# template_atmega328p.net
KiCad netlist of a schematic drawn in EAGLE
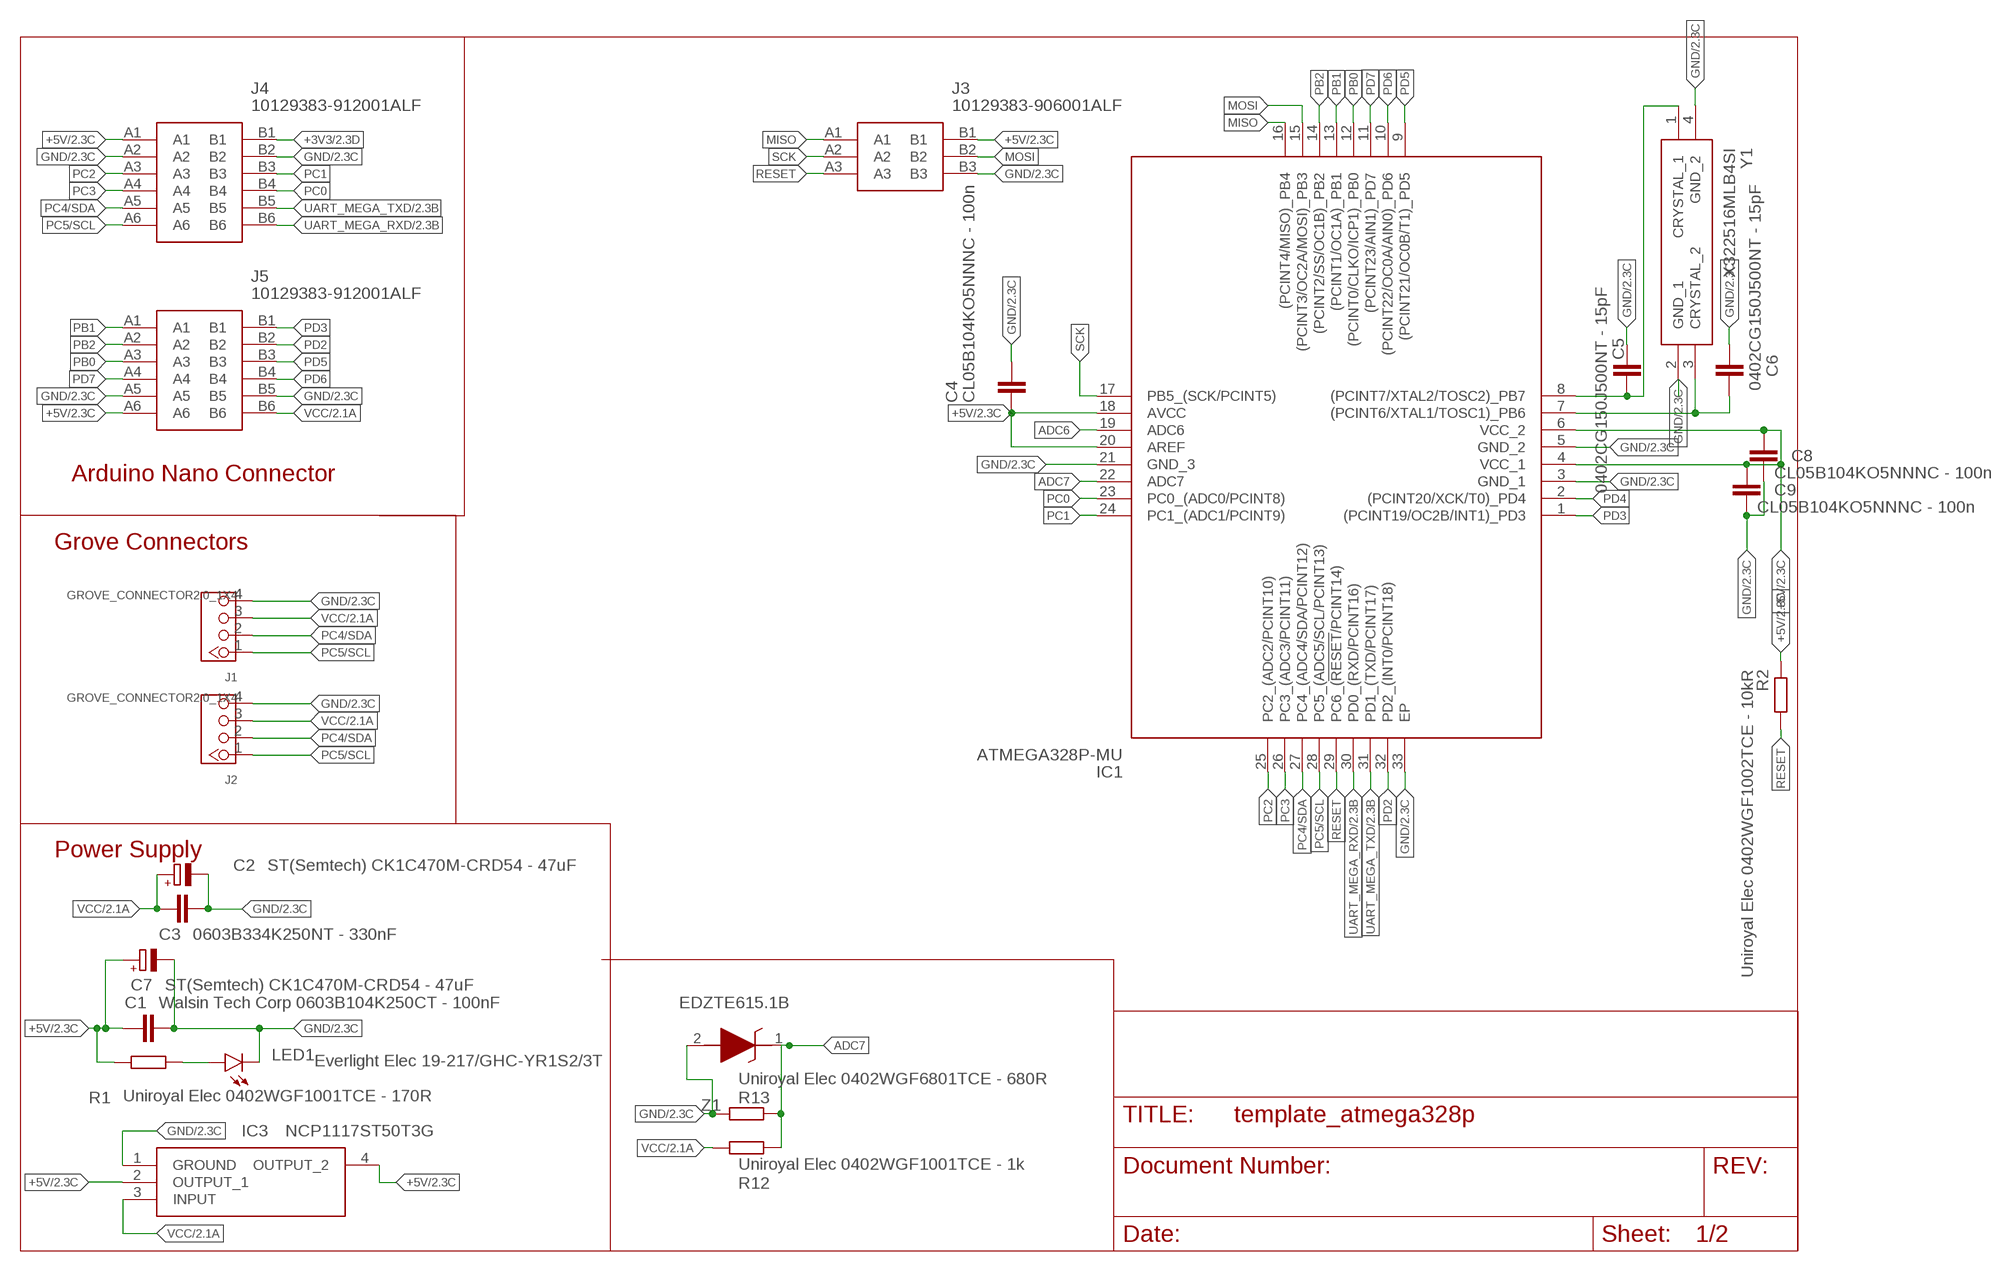
[diagram p0: schematic, sheet 1]
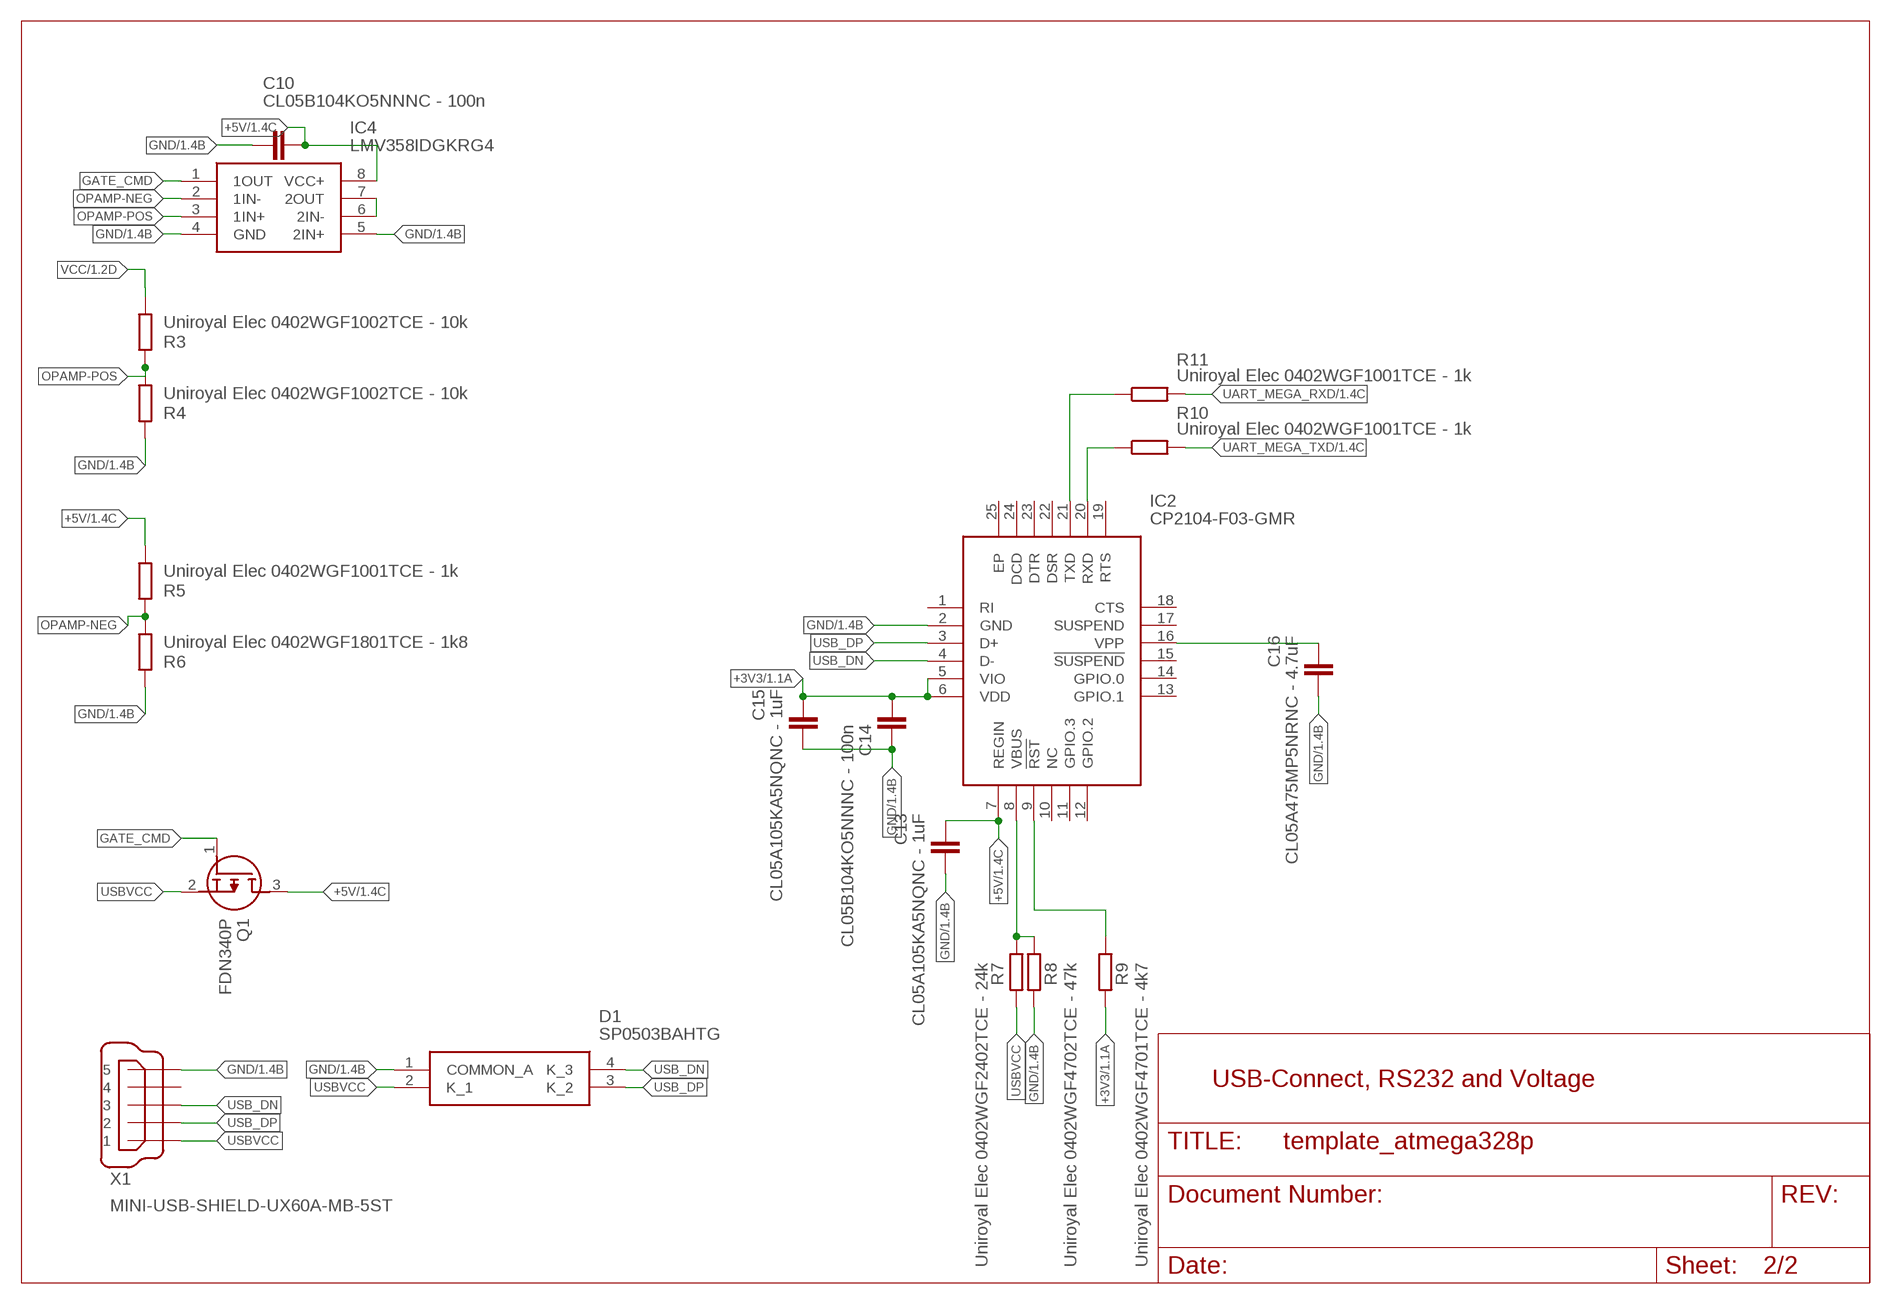
[diagram p1: schematic, sheet 2]

(export (version "E")
  (design (tool "Eeschema 10.0.6"))
  (components
    (comp (ref "C1")
      (value "Walsin Tech Corp 0603B104K250CT - 100nF")
      (footprint "eagle-import:C0603")
      (libsource (lib "eagle-import") (part "C-EUC0603"))
    )
    (comp (ref "C2")
      (value "ST(Semtech) CK1C470M-CRD54 - 47uF")
      (footprint "eagle-import:PANASONIC_C")
      (libsource (lib "eagle-import") (part "CPOL-EUC"))
    )
    (comp (ref "C3")
      (value "0603B334K250NT - 330nF")
      (footprint "eagle-import:C0603")
      (libsource (lib "eagle-import") (part "C-EUC0603"))
    )
    (comp (ref "C4")
      (value "CL05B104KO5NNNC - 100n")
      (footprint "eagle-import:C0402")
      (libsource (lib "eagle-import") (part "C-EUC0402"))
    )
    (comp (ref "C5")
      (value "0402CG150J500NT - 15pF")
      (footprint "eagle-import:C0402")
      (libsource (lib "eagle-import") (part "C-EUC0402"))
    )
    (comp (ref "C6")
      (value "0402CG150J500NT - 15pF")
      (footprint "eagle-import:C0402")
      (libsource (lib "eagle-import") (part "C-EUC0402"))
    )
    (comp (ref "C7")
      (value "ST(Semtech) CK1C470M-CRD54 - 47uF")
      (footprint "eagle-import:PANASONIC_C")
      (libsource (lib "eagle-import") (part "CPOL-EUC"))
    )
    (comp (ref "C8")
      (value "CL05B104KO5NNNC - 100n")
      (footprint "eagle-import:C0402")
      (libsource (lib "eagle-import") (part "C-EUC0402"))
    )
    (comp (ref "C9")
      (value "CL05B104KO5NNNC - 100n")
      (footprint "eagle-import:C0402")
      (libsource (lib "eagle-import") (part "C-EUC0402"))
    )
    (comp (ref "IC1")
      (value "ATMEGA328P-MU")
      (footprint "eagle-import:QFN50P500X500X100-33N")
      (fields (field (name "MOUSER_PART_NUMBER") "556-ATMEGA328P-MU"))
      (libsource (lib "eagle-import") (part "ATMEGA328P-MU"))
    )
    (comp (ref "IC3")
      (value "NCP1117ST50T3G")
      (footprint "eagle-import:SOT230P700X180-4N@1")
      (fields (field (name "MOUSER_PART_NUMBER") "863-NCP1117ST50T3G"))
      (libsource (lib "eagle-import") (part "NCP1117ST50T3G"))
    )
    (comp (ref "J1")
      (value "GROVE_CONNECTOR2.0_1X4")
      (footprint "eagle-import:2.0_1X4_STRAIGHT")
      (libsource (lib "eagle-import") (part "GROVE_CONNECTOR2.0_1X4"))
    )
    (comp (ref "J2")
      (value "GROVE_CONNECTOR2.0_1X4")
      (footprint "eagle-import:2.0_1X4_STRAIGHT")
      (libsource (lib "eagle-import") (part "GROVE_CONNECTOR2.0_1X4"))
    )
    (comp (ref "J3")
      (value "10129383-906001ALF")
      (footprint "eagle-import:10129383906001ALF")
      (fields (field (name "MOUSER_PART_NUMBER") "649-1012938390601ALF"))
      (libsource (lib "eagle-import") (part "10129383-906001ALF"))
    )
    (comp (ref "J4")
      (value "10129383-912001ALF")
      (footprint "eagle-import:10129383912001ALF")
      (fields (field (name "MOUSER_PART_NUMBER") "649-1012938391201ALF"))
      (libsource (lib "eagle-import") (part "10129383-912001ALF"))
    )
    (comp (ref "J5")
      (value "10129383-912001ALF")
      (footprint "eagle-import:10129383912001ALF")
      (fields (field (name "MOUSER_PART_NUMBER") "649-1012938391201ALF"))
      (libsource (lib "eagle-import") (part "10129383-912001ALF"))
    )
    (comp (ref "LED1")
      (value "Everlight Elec 19-217/GHC-YR1S2/3T")
      (footprint "eagle-import:CHIPLED_0603")
      (libsource (lib "eagle-import") (part "LEDCHIPLED_0603"))
    )
    (comp (ref "R1")
      (value "Uniroyal Elec 0402WGF1001TCE - 170R")
      (footprint "eagle-import:R0402")
      (libsource (lib "eagle-import") (part "R-EU_R0402"))
    )
    (comp (ref "R2")
      (value "Uniroyal Elec 0402WGF1002TCE - 10kR")
      (footprint "eagle-import:R0402")
      (libsource (lib "eagle-import") (part "R-EU_R0402"))
    )
    (comp (ref "R12")
      (value "Uniroyal Elec 0402WGF1001TCE - 1k")
      (footprint "eagle-import:R0402")
      (libsource (lib "eagle-import") (part "R-EU_R0402"))
    )
    (comp (ref "R13")
      (value "Uniroyal Elec 0402WGF6801TCE - 680R")
      (footprint "eagle-import:R0402")
      (libsource (lib "eagle-import") (part "R-EU_R0402"))
    )
    (comp (ref "Y1")
      (value "X322516MLB4SI")
      (footprint "eagle-import:X322516MLB4SI")
      (libsource (lib "eagle-import") (part "X322516MLB4SI"))
    )
    (comp (ref "Z1")
      (value "EDZTE615.1B")
      (footprint "eagle-import:EMD2")
      (fields (field (name "MOUSER_PART_NUMBER") "755-EDZTE615.1B"))
      (libsource (lib "eagle-import") (part "EDZTE615.1B"))
    )
    (comp (ref "C10")
      (value "CL05B104KO5NNNC - 100n")
      (footprint "eagle-import:C0402")
      (libsource (lib "eagle-import") (part "C-EUC0402"))
    )
    (comp (ref "C13")
      (value "CL05A105KA5NQNC - 1uF")
      (footprint "eagle-import:C0402")
      (libsource (lib "eagle-import") (part "C-EUC0402"))
    )
    (comp (ref "C14")
      (value "CL05B104KO5NNNC - 100n")
      (footprint "eagle-import:C0402")
      (libsource (lib "eagle-import") (part "C-EUC0402"))
    )
    (comp (ref "C15")
      (value "CL05A105KA5NQNC - 1uF")
      (footprint "eagle-import:C0402")
      (libsource (lib "eagle-import") (part "C-EUC0402"))
    )
    (comp (ref "C16")
      (value "CL05A475MP5NRNC - 4.7uF")
      (footprint "eagle-import:C0402")
      (libsource (lib "eagle-import") (part "C-EUC0402"))
    )
    (comp (ref "D1")
      (value "SP0503BAHTG")
      (footprint "eagle-import:SP0503BAHTG")
      (fields (field (name "MOUSER_PART_NUMBER") "576-SP0503BAHTG"))
      (libsource (lib "eagle-import") (part "SP0503BAHTG"))
    )
    (comp (ref "IC2")
      (value "CP2104-F03-GMR")
      (footprint "eagle-import:QFN50P400X400X80-25N")
      (fields (field (name "MOUSER_PART_NUMBER") "634-CP2104-F03-GMR"))
      (libsource (lib "eagle-import") (part "CP2104-F03-GMR"))
    )
    (comp (ref "IC4")
      (value "LMV358IDGKRG4")
      (footprint "eagle-import:SOP65P490X110-8N")
      (fields (field (name "MOUSER_PART_NUMBER") "595-LMV358IDGKRG4"))
      (libsource (lib "eagle-import") (part "LMV358IDGKRG4"))
    )
    (comp (ref "Q1")
      (value "FDN340P")
      (footprint "eagle-import:SOT95P237X112-3N")
      (fields (field (name "MOUSER_PART_NUMBER") "512-FDN340P"))
      (libsource (lib "eagle-import") (part "FDN340P"))
    )
    (comp (ref "R3")
      (value "Uniroyal Elec 0402WGF1002TCE - 10k")
      (footprint "eagle-import:R0402")
      (libsource (lib "eagle-import") (part "R-EU_R0402"))
    )
    (comp (ref "R4")
      (value "Uniroyal Elec 0402WGF1002TCE - 10k")
      (footprint "eagle-import:R0402")
      (libsource (lib "eagle-import") (part "R-EU_R0402"))
    )
    (comp (ref "R5")
      (value "Uniroyal Elec 0402WGF1001TCE - 1k")
      (footprint "eagle-import:R0402")
      (libsource (lib "eagle-import") (part "R-EU_R0402"))
    )
    (comp (ref "R6")
      (value "Uniroyal Elec 0402WGF1801TCE - 1k8")
      (footprint "eagle-import:R0402")
      (libsource (lib "eagle-import") (part "R-EU_R0402"))
    )
    (comp (ref "R7")
      (value "Uniroyal Elec 0402WGF2402TCE - 24k")
      (footprint "eagle-import:R0402")
      (libsource (lib "eagle-import") (part "R-EU_R0402"))
    )
    (comp (ref "R8")
      (value "Uniroyal Elec 0402WGF4702TCE - 47k")
      (footprint "eagle-import:R0402")
      (libsource (lib "eagle-import") (part "R-EU_R0402"))
    )
    (comp (ref "R9")
      (value "Uniroyal Elec 0402WGF4701TCE - 4k7")
      (footprint "eagle-import:R0402")
      (libsource (lib "eagle-import") (part "R-EU_R0402"))
    )
    (comp (ref "R10")
      (value "Uniroyal Elec 0402WGF1001TCE - 1k")
      (footprint "eagle-import:R0402")
      (libsource (lib "eagle-import") (part "R-EU_R0402"))
    )
    (comp (ref "R11")
      (value "Uniroyal Elec 0402WGF1001TCE - 1k")
      (footprint "eagle-import:R0402")
      (libsource (lib "eagle-import") (part "R-EU_R0402"))
    )
    (comp (ref "X1")
      (value "MINI-USB-SHIELD-UX60A-MB-5ST")
      (footprint "eagle-import:UX60A-MB-5ST")
      (libsource (lib "eagle-import") (part "MINI-USB-SHIELD-UX60A-MB-5ST"))
    )
  )
  (nets
    (net (code "1") (name "+3V3") (class "Default")
      (node (ref "C14") (pin "2") (pinfunction "2_2") (pintype "passive"))
      (node (ref "C15") (pin "2") (pinfunction "2_2") (pintype "passive"))
      (node (ref "IC2") (pin "5") (pinfunction "VIO_5") (pintype "bidirectional"))
      (node (ref "IC2") (pin "6") (pinfunction "VDD_6") (pintype "bidirectional"))
      (node (ref "J4") (pin "B1") (pinfunction "B1_B1") (pintype "bidirectional"))
      (node (ref "R9") (pin "2") (pinfunction "2_2") (pintype "passive"))
    )
    (net (code "2") (name "+5V") (class "Default")
      (node (ref "C1") (pin "1") (pinfunction "1_1") (pintype "passive"))
      (node (ref "C10") (pin "2") (pinfunction "2_2") (pintype "passive"))
      (node (ref "C13") (pin "2") (pinfunction "2_2") (pintype "passive"))
      (node (ref "C4") (pin "1") (pinfunction "1_1") (pintype "passive"))
      (node (ref "C7") (pin "+") (pinfunction "+_+") (pintype "passive"))
      (node (ref "C8") (pin "2") (pinfunction "2_2") (pintype "passive"))
      (node (ref "C9") (pin "2") (pinfunction "2_2") (pintype "passive"))
      (node (ref "IC1") (pin "18") (pinfunction "AVCC_18") (pintype "bidirectional"))
      (node (ref "IC1") (pin "20") (pinfunction "AREF_20") (pintype "bidirectional"))
      (node (ref "IC1") (pin "4") (pinfunction "VCC_1_4") (pintype "bidirectional"))
      (node (ref "IC1") (pin "6") (pinfunction "VCC_2_6") (pintype "bidirectional"))
      (node (ref "IC2") (pin "7") (pinfunction "REGIN_7") (pintype "bidirectional"))
      (node (ref "IC3") (pin "2") (pinfunction "OUTPUT_1_2") (pintype "bidirectional"))
      (node (ref "IC3") (pin "4") (pinfunction "OUTPUT_2_4") (pintype "bidirectional"))
      (node (ref "IC4") (pin "8") (pinfunction "VCC+_8") (pintype "bidirectional"))
      (node (ref "J3") (pin "B1") (pinfunction "B1_B1") (pintype "bidirectional"))
      (node (ref "J4") (pin "A1") (pinfunction "A1_A1") (pintype "bidirectional"))
      (node (ref "J5") (pin "A6") (pinfunction "A6_A6") (pintype "bidirectional"))
      (node (ref "Q1") (pin "3") (pinfunction "D_3") (pintype "bidirectional"))
      (node (ref "R1") (pin "2") (pinfunction "2_2") (pintype "passive"))
      (node (ref "R2") (pin "2") (pinfunction "2_2") (pintype "passive"))
      (node (ref "R5") (pin "1") (pinfunction "1_1") (pintype "passive"))
    )
    (net (code "3") (name "ADC6") (class "Default")
      (node (ref "IC1") (pin "19") (pinfunction "ADC6_19") (pintype "bidirectional"))
    )
    (net (code "4") (name "ADC7") (class "Default")
      (node (ref "IC1") (pin "22") (pinfunction "ADC7_22") (pintype "bidirectional"))
      (node (ref "R12") (pin "1") (pinfunction "1_1") (pintype "passive"))
      (node (ref "R13") (pin "2") (pinfunction "2_2") (pintype "passive"))
      (node (ref "Z1") (pin "1") (pinfunction "K_1") (pintype "bidirectional"))
    )
    (net (code "5") (name "GATE_CMD") (class "Default")
      (node (ref "IC4") (pin "1") (pinfunction "1OUT_1") (pintype "bidirectional"))
      (node (ref "Q1") (pin "1") (pinfunction "G_1") (pintype "bidirectional"))
    )
    (net (code "6") (name "GND") (class "Default")
      (node (ref "C1") (pin "2") (pinfunction "2_2") (pintype "passive"))
      (node (ref "C10") (pin "1") (pinfunction "1_1") (pintype "passive"))
      (node (ref "C13") (pin "1") (pinfunction "1_1") (pintype "passive"))
      (node (ref "C14") (pin "1") (pinfunction "1_1") (pintype "passive"))
      (node (ref "C15") (pin "1") (pinfunction "1_1") (pintype "passive"))
      (node (ref "C16") (pin "1") (pinfunction "1_1") (pintype "passive"))
      (node (ref "C2") (pin "-") (pinfunction "-_-") (pintype "passive"))
      (node (ref "C3") (pin "1") (pinfunction "1_1") (pintype "passive"))
      (node (ref "C4") (pin "2") (pinfunction "2_2") (pintype "passive"))
      (node (ref "C5") (pin "1") (pinfunction "1_1") (pintype "passive"))
      (node (ref "C6") (pin "1") (pinfunction "1_1") (pintype "passive"))
      (node (ref "C7") (pin "-") (pinfunction "-_-") (pintype "passive"))
      (node (ref "C8") (pin "1") (pinfunction "1_1") (pintype "passive"))
      (node (ref "C9") (pin "1") (pinfunction "1_1") (pintype "passive"))
      (node (ref "D1") (pin "1") (pinfunction "COMMON_A_1") (pintype "bidirectional"))
      (node (ref "IC1") (pin "21") (pinfunction "GND_3_21") (pintype "bidirectional"))
      (node (ref "IC1") (pin "3") (pinfunction "GND_1_3") (pintype "bidirectional"))
      (node (ref "IC1") (pin "33") (pinfunction "EP_33") (pintype "bidirectional"))
      (node (ref "IC1") (pin "5") (pinfunction "GND_2_5") (pintype "bidirectional"))
      (node (ref "IC2") (pin "2") (pinfunction "GND_2") (pintype "bidirectional"))
      (node (ref "IC3") (pin "1") (pinfunction "GROUND_1") (pintype "bidirectional"))
      (node (ref "IC4") (pin "4") (pinfunction "GND_4") (pintype "bidirectional"))
      (node (ref "IC4") (pin "5") (pinfunction "2IN+_5") (pintype "bidirectional"))
      (node (ref "J1") (pin "4") (pinfunction "4_4") (pintype "bidirectional"))
      (node (ref "J2") (pin "4") (pinfunction "4_4") (pintype "bidirectional"))
      (node (ref "J3") (pin "B3") (pinfunction "B3_B3") (pintype "bidirectional"))
      (node (ref "J4") (pin "A2") (pinfunction "A2_A2") (pintype "bidirectional"))
      (node (ref "J4") (pin "B2") (pinfunction "B2_B2") (pintype "bidirectional"))
      (node (ref "J5") (pin "A5") (pinfunction "A5_A5") (pintype "bidirectional"))
      (node (ref "J5") (pin "B5") (pinfunction "B5_B5") (pintype "bidirectional"))
      (node (ref "LED1") (pin "C") (pinfunction "C_C") (pintype "passive"))
      (node (ref "R13") (pin "1") (pinfunction "1_1") (pintype "passive"))
      (node (ref "R4") (pin "2") (pinfunction "2_2") (pintype "passive"))
      (node (ref "R6") (pin "2") (pinfunction "2_2") (pintype "passive"))
      (node (ref "R8") (pin "2") (pinfunction "2_2") (pintype "passive"))
      (node (ref "X1") (pin "5") (pinfunction "5_5") (pintype "input"))
      (node (ref "Y1") (pin "2") (pinfunction "GND_1_2") (pintype "bidirectional"))
      (node (ref "Y1") (pin "4") (pinfunction "GND_2_4") (pintype "bidirectional"))
      (node (ref "Z1") (pin "2") (pinfunction "A_2") (pintype "bidirectional"))
    )
    (net (code "7") (name "MISO") (class "Default")
      (node (ref "IC1") (pin "16") (pinfunction "(PCINT4/MISO)_PB4_16") (pintype "bidirectional"))
      (node (ref "J3") (pin "A1") (pinfunction "A1_A1") (pintype "bidirectional"))
    )
    (net (code "8") (name "MOSI") (class "Default")
      (node (ref "IC1") (pin "15") (pinfunction "(PCINT3/OC2A/MOSI)_PB3_15") (pintype "bidirectional"))
      (node (ref "J3") (pin "B2") (pinfunction "B2_B2") (pintype "bidirectional"))
    )
    (net (code "9") (name "Net-(IC1-(PCINT6{slash}XTAL1{slash}TOSC1)_PB6)") (class "Default")
      (node (ref "C6") (pin "2") (pinfunction "2_2") (pintype "passive"))
      (node (ref "IC1") (pin "7") (pinfunction "(PCINT6/XTAL1/TOSC1)_PB6_7") (pintype "bidirectional"))
      (node (ref "Y1") (pin "3") (pinfunction "CRYSTAL_2_3") (pintype "bidirectional"))
    )
    (net (code "10") (name "Net-(IC1-(PCINT7{slash}XTAL2{slash}TOSC2)_PB7)") (class "Default")
      (node (ref "C5") (pin "2") (pinfunction "2_2") (pintype "passive"))
      (node (ref "IC1") (pin "8") (pinfunction "(PCINT7/XTAL2/TOSC2)_PB7_8") (pintype "bidirectional"))
      (node (ref "Y1") (pin "1") (pinfunction "CRYSTAL_1_1") (pintype "bidirectional"))
    )
    (net (code "11") (name "Net-(IC2-RXD)") (class "Default")
      (node (ref "IC2") (pin "20") (pinfunction "RXD_20") (pintype "bidirectional"))
      (node (ref "R10") (pin "1") (pinfunction "1_1") (pintype "passive"))
    )
    (net (code "12") (name "Net-(IC2-TXD)") (class "Default")
      (node (ref "IC2") (pin "21") (pinfunction "TXD_21") (pintype "bidirectional"))
      (node (ref "R11") (pin "1") (pinfunction "1_1") (pintype "passive"))
    )
    (net (code "13") (name "Net-(IC2-VBUS)") (class "Default")
      (node (ref "IC2") (pin "8") (pinfunction "VBUS_8") (pintype "bidirectional"))
      (node (ref "R7") (pin "1") (pinfunction "1_1") (pintype "passive"))
      (node (ref "R8") (pin "1") (pinfunction "1_1") (pintype "passive"))
    )
    (net (code "14") (name "Net-(IC2-VPP)") (class "Default")
      (node (ref "C16") (pin "2") (pinfunction "2_2") (pintype "passive"))
      (node (ref "IC2") (pin "16") (pinfunction "VPP_16") (pintype "bidirectional"))
    )
    (net (code "15") (name "Net-(IC2-~{RST})") (class "Default")
      (node (ref "IC2") (pin "9") (pinfunction "~{RST}_9") (pintype "bidirectional"))
      (node (ref "R9") (pin "1") (pinfunction "1_1") (pintype "passive"))
    )
    (net (code "16") (name "Net-(IC4-2IN-)") (class "Default")
      (node (ref "IC4") (pin "6") (pinfunction "2IN-_6") (pintype "bidirectional"))
      (node (ref "IC4") (pin "7") (pinfunction "2OUT_7") (pintype "bidirectional"))
    )
    (net (code "17") (name "Net-(LED1-PadA)") (class "Default")
      (node (ref "LED1") (pin "A") (pinfunction "A_A") (pintype "passive"))
      (node (ref "R1") (pin "1") (pinfunction "1_1") (pintype "passive"))
    )
    (net (code "18") (name "OPAMP-NEG") (class "Default")
      (node (ref "IC4") (pin "2") (pinfunction "1IN-_2") (pintype "bidirectional"))
      (node (ref "R5") (pin "2") (pinfunction "2_2") (pintype "passive"))
      (node (ref "R6") (pin "1") (pinfunction "1_1") (pintype "passive"))
    )
    (net (code "19") (name "OPAMP-POS") (class "Default")
      (node (ref "IC4") (pin "3") (pinfunction "1IN+_3") (pintype "bidirectional"))
      (node (ref "R3") (pin "2") (pinfunction "2_2") (pintype "passive"))
      (node (ref "R4") (pin "1") (pinfunction "1_1") (pintype "passive"))
    )
    (net (code "20") (name "PB0") (class "Default")
      (node (ref "IC1") (pin "12") (pinfunction "(PCINT0/CLKO/ICP1)_PB0_12") (pintype "bidirectional"))
      (node (ref "J5") (pin "A3") (pinfunction "A3_A3") (pintype "bidirectional"))
    )
    (net (code "21") (name "PB1") (class "Default")
      (node (ref "IC1") (pin "13") (pinfunction "(PCINT1/OC1A)_PB1_13") (pintype "bidirectional"))
      (node (ref "J5") (pin "A1") (pinfunction "A1_A1") (pintype "bidirectional"))
    )
    (net (code "22") (name "PB2") (class "Default")
      (node (ref "IC1") (pin "14") (pinfunction "(PCINT2/SS/OC1B)_PB2_14") (pintype "bidirectional"))
      (node (ref "J5") (pin "A2") (pinfunction "A2_A2") (pintype "bidirectional"))
    )
    (net (code "23") (name "PC0") (class "Default")
      (node (ref "IC1") (pin "23") (pinfunction "PC0_(ADC0/PCINT8)_23") (pintype "bidirectional"))
      (node (ref "J4") (pin "B4") (pinfunction "B4_B4") (pintype "bidirectional"))
    )
    (net (code "24") (name "PC1") (class "Default")
      (node (ref "IC1") (pin "24") (pinfunction "PC1_(ADC1/PCINT9)_24") (pintype "bidirectional"))
      (node (ref "J4") (pin "B3") (pinfunction "B3_B3") (pintype "bidirectional"))
    )
    (net (code "25") (name "PC2") (class "Default")
      (node (ref "IC1") (pin "25") (pinfunction "PC2_(ADC2/PCINT10)_25") (pintype "bidirectional"))
      (node (ref "J4") (pin "A3") (pinfunction "A3_A3") (pintype "bidirectional"))
    )
    (net (code "26") (name "PC3") (class "Default")
      (node (ref "IC1") (pin "26") (pinfunction "PC3_(ADC3/PCINT11)_26") (pintype "bidirectional"))
      (node (ref "J4") (pin "A4") (pinfunction "A4_A4") (pintype "bidirectional"))
    )
    (net (code "27") (name "PC4{slash}SDA") (class "Default")
      (node (ref "IC1") (pin "27") (pinfunction "PC4_(ADC4/SDA/PCINT12)_27") (pintype "bidirectional"))
      (node (ref "J1") (pin "2") (pinfunction "2_2") (pintype "bidirectional"))
      (node (ref "J2") (pin "2") (pinfunction "2_2") (pintype "bidirectional"))
      (node (ref "J4") (pin "A5") (pinfunction "A5_A5") (pintype "bidirectional"))
    )
    (net (code "28") (name "PC5{slash}SCL") (class "Default")
      (node (ref "IC1") (pin "28") (pinfunction "PC5_(ADC5/SCL/PCINT13)_28") (pintype "bidirectional"))
      (node (ref "J1") (pin "1") (pinfunction "1_1") (pintype "bidirectional"))
      (node (ref "J2") (pin "1") (pinfunction "1_1") (pintype "bidirectional"))
      (node (ref "J4") (pin "A6") (pinfunction "A6_A6") (pintype "bidirectional"))
    )
    (net (code "29") (name "PD2") (class "Default")
      (node (ref "IC1") (pin "32") (pinfunction "PD2_(INT0/PCINT18)_32") (pintype "bidirectional"))
      (node (ref "J5") (pin "B2") (pinfunction "B2_B2") (pintype "bidirectional"))
    )
    (net (code "30") (name "PD3") (class "Default")
      (node (ref "IC1") (pin "1") (pinfunction "(PCINT19/OC2B/INT1)_PD3_1") (pintype "bidirectional"))
      (node (ref "J5") (pin "B1") (pinfunction "B1_B1") (pintype "bidirectional"))
    )
    (net (code "31") (name "PD4") (class "Default")
      (node (ref "IC1") (pin "2") (pinfunction "(PCINT20/XCK/T0)_PD4_2") (pintype "bidirectional"))
    )
    (net (code "32") (name "PD5") (class "Default")
      (node (ref "IC1") (pin "9") (pinfunction "(PCINT21/OC0B/T1)_PD5_9") (pintype "bidirectional"))
      (node (ref "J5") (pin "B3") (pinfunction "B3_B3") (pintype "bidirectional"))
    )
    (net (code "33") (name "PD6") (class "Default")
      (node (ref "IC1") (pin "10") (pinfunction "(PCINT22/OC0A/AIN0)_PD6_10") (pintype "bidirectional"))
      (node (ref "J5") (pin "B4") (pinfunction "B4_B4") (pintype "bidirectional"))
    )
    (net (code "34") (name "PD7") (class "Default")
      (node (ref "IC1") (pin "11") (pinfunction "(PCINT23/AIN1)_PD7_11") (pintype "bidirectional"))
      (node (ref "J5") (pin "A4") (pinfunction "A4_A4") (pintype "bidirectional"))
    )
    (net (code "35") (name "RESET") (class "Default")
      (node (ref "IC1") (pin "29") (pinfunction "PC6_(~{RESET}/PCINT14)_29") (pintype "bidirectional"))
      (node (ref "J3") (pin "A3") (pinfunction "A3_A3") (pintype "bidirectional"))
      (node (ref "R2") (pin "1") (pinfunction "1_1") (pintype "passive"))
    )
    (net (code "36") (name "SCK") (class "Default")
      (node (ref "IC1") (pin "17") (pinfunction "PB5_(SCK/PCINT5)_17") (pintype "bidirectional"))
      (node (ref "J3") (pin "A2") (pinfunction "A2_A2") (pintype "bidirectional"))
    )
    (net (code "37") (name "UART_MEGA_RXD") (class "Default")
      (node (ref "IC1") (pin "30") (pinfunction "PD0_(RXD/PCINT16)_30") (pintype "bidirectional"))
      (node (ref "J4") (pin "B6") (pinfunction "B6_B6") (pintype "bidirectional"))
      (node (ref "R11") (pin "2") (pinfunction "2_2") (pintype "passive"))
    )
    (net (code "38") (name "UART_MEGA_TXD") (class "Default")
      (node (ref "IC1") (pin "31") (pinfunction "PD1_(TXD/PCINT17)_31") (pintype "bidirectional"))
      (node (ref "J4") (pin "B5") (pinfunction "B5_B5") (pintype "bidirectional"))
      (node (ref "R10") (pin "2") (pinfunction "2_2") (pintype "passive"))
    )
    (net (code "39") (name "USBVCC") (class "Default")
      (node (ref "D1") (pin "2") (pinfunction "K_1_2") (pintype "bidirectional"))
      (node (ref "Q1") (pin "2") (pinfunction "S_2") (pintype "bidirectional"))
      (node (ref "R7") (pin "2") (pinfunction "2_2") (pintype "passive"))
      (node (ref "X1") (pin "1") (pinfunction "1_1") (pintype "input"))
    )
    (net (code "40") (name "USB_DN") (class "Default")
      (node (ref "D1") (pin "4") (pinfunction "K_3_4") (pintype "bidirectional"))
      (node (ref "IC2") (pin "4") (pinfunction "D-_4") (pintype "bidirectional"))
      (node (ref "X1") (pin "3") (pinfunction "3_3") (pintype "input"))
    )
    (net (code "41") (name "USB_DP") (class "Default")
      (node (ref "D1") (pin "3") (pinfunction "K_2_3") (pintype "bidirectional"))
      (node (ref "IC2") (pin "3") (pinfunction "D+_3") (pintype "bidirectional"))
      (node (ref "X1") (pin "2") (pinfunction "2_2") (pintype "input"))
    )
    (net (code "42") (name "VCC") (class "Default")
      (node (ref "C2") (pin "+") (pinfunction "+_+") (pintype "passive"))
      (node (ref "C3") (pin "2") (pinfunction "2_2") (pintype "passive"))
      (node (ref "IC3") (pin "3") (pinfunction "INPUT_3") (pintype "bidirectional"))
      (node (ref "J1") (pin "3") (pinfunction "3_3") (pintype "bidirectional"))
      (node (ref "J2") (pin "3") (pinfunction "3_3") (pintype "bidirectional"))
      (node (ref "J5") (pin "B6") (pinfunction "B6_B6") (pintype "bidirectional"))
      (node (ref "R12") (pin "2") (pinfunction "2_2") (pintype "passive"))
      (node (ref "R3") (pin "1") (pinfunction "1_1") (pintype "passive"))
    )
    (net (code "43") (name "unconnected-(IC2-CTS-Pad18)") (class "Default")
      (node (ref "IC2") (pin "18") (pinfunction "CTS_18") (pintype "bidirectional"))
    )
    (net (code "44") (name "unconnected-(IC2-DCD-Pad24)") (class "Default")
      (node (ref "IC2") (pin "24") (pinfunction "DCD_24") (pintype "bidirectional"))
    )
    (net (code "45") (name "unconnected-(IC2-DSR-Pad22)") (class "Default")
      (node (ref "IC2") (pin "22") (pinfunction "DSR_22") (pintype "bidirectional"))
    )
    (net (code "46") (name "unconnected-(IC2-DTR-Pad23)") (class "Default")
      (node (ref "IC2") (pin "23") (pinfunction "DTR_23") (pintype "bidirectional"))
    )
    (net (code "47") (name "unconnected-(IC2-EP-Pad25)") (class "Default")
      (node (ref "IC2") (pin "25") (pinfunction "EP_25") (pintype "bidirectional"))
    )
    (net (code "48") (name "unconnected-(IC2-GPIO.0-Pad14)") (class "Default")
      (node (ref "IC2") (pin "14") (pinfunction "GPIO.0_14") (pintype "bidirectional"))
    )
    (net (code "49") (name "unconnected-(IC2-GPIO.1-Pad13)") (class "Default")
      (node (ref "IC2") (pin "13") (pinfunction "GPIO.1_13") (pintype "bidirectional"))
    )
    (net (code "50") (name "unconnected-(IC2-GPIO.2-Pad12)") (class "Default")
      (node (ref "IC2") (pin "12") (pinfunction "GPIO.2_12") (pintype "bidirectional"))
    )
    (net (code "51") (name "unconnected-(IC2-GPIO.3-Pad11)") (class "Default")
      (node (ref "IC2") (pin "11") (pinfunction "GPIO.3_11") (pintype "bidirectional"))
    )
    (net (code "52") (name "unconnected-(IC2-NC-Pad10)") (class "Default")
      (node (ref "IC2") (pin "10") (pinfunction "NC_10") (pintype "no_connect"))
    )
    (net (code "53") (name "unconnected-(IC2-RI-Pad1)") (class "Default")
      (node (ref "IC2") (pin "1") (pinfunction "RI_1") (pintype "bidirectional"))
    )
    (net (code "54") (name "unconnected-(IC2-RTS-Pad19)") (class "Default")
      (node (ref "IC2") (pin "19") (pinfunction "RTS_19") (pintype "bidirectional"))
    )
    (net (code "55") (name "unconnected-(IC2-SUSPEND-Pad17)") (class "Default")
      (node (ref "IC2") (pin "17") (pinfunction "SUSPEND_17") (pintype "bidirectional"))
    )
    (net (code "56") (name "unconnected-(IC2-~{SUSPEND}-Pad15)") (class "Default")
      (node (ref "IC2") (pin "15") (pinfunction "~{SUSPEND}_15") (pintype "bidirectional"))
    )
    (net (code "57") (name "unconnected-(X1-Pad4)") (class "Default")
      (node (ref "X1") (pin "4") (pinfunction "4_4") (pintype "input"))
    )
  )
)
